# Voeding.net
KiCad netlist of a schematic drawn in Altium Designer
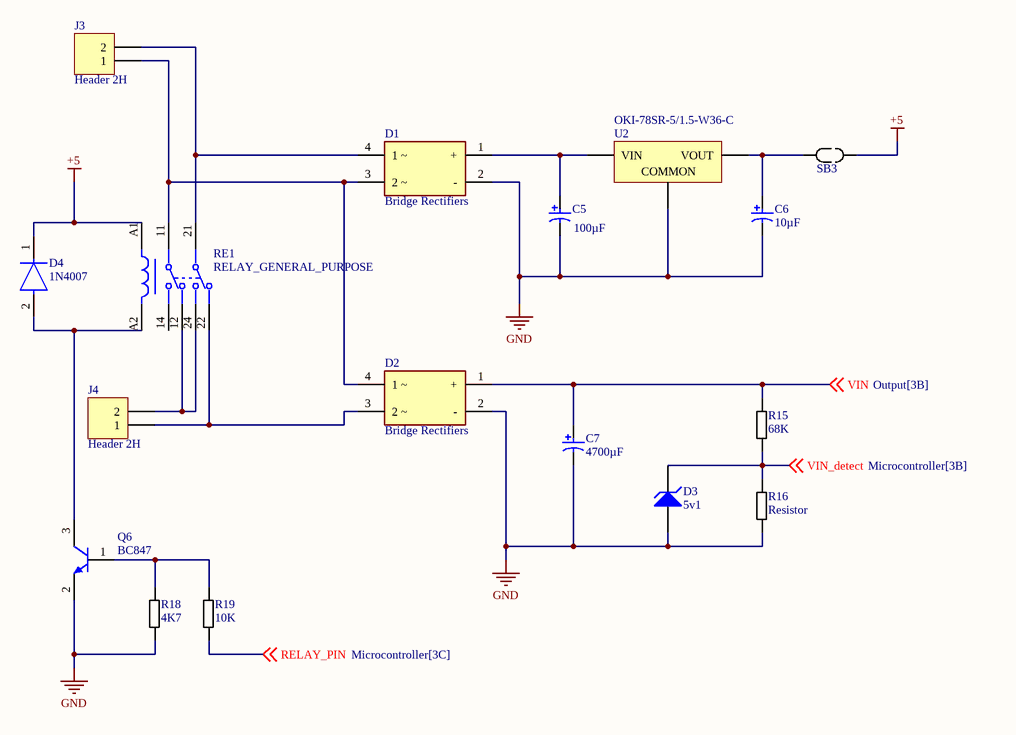
[diagram p0: Voeding.SchDoc]

(export (version "E")
  (design (tool "Eeschema 10.0.6"))
  (components
    (comp (ref "C5")
      (value "100µF")
      (footprint "CAP-SMD_BD8.0-L8.3-W8.3-FD")
      (fields (field (name "MANUFACTURER") "Panasonic"))
      (libsource (lib "Soldeerstation") (part "Electrolytic capacitor"))
    )
    (comp (ref "C6")
      (value "10µF")
      (footprint "CAP-SMD_BD4.0-L4.3-W4.3-FD-LS5.3")
      (fields (field (name "MANUFACTURER") "Panasonic"))
      (libsource (lib "Soldeerstation") (part "Electrolytic capacitor"))
    )
    (comp (ref "C7")
      (value "4700µF")
      (footprint "CAP-TH_BD25.0-P10.00-D1.4-FD")
      (fields (field (name "MANUFACTURER") "Panasonic"))
      (libsource (lib "Soldeerstation") (part "Electrolytic capacitor"))
    )
    (comp (ref "D1")
      (value "Bridge Rectifiers")
      (footprint "TTF")
      (fields
        (field (name "OCTOPART") "https://octopart.com/gbpc3510w+t0-taiwan+semiconductor-12450781")
        (field (name "MANUFACTURER PART NUMBER") "GBPC3510W T0")
        (field (name "MANUFACTURER") "Taiwan Semiconductor")
      )
      (libsource (lib "Soldeerstation") (part "Bridge Rectifiers"))
    )
    (comp (ref "D2")
      (value "Bridge Rectifiers")
      (footprint "TTF")
      (fields
        (field (name "OCTOPART") "https://octopart.com/gbpc3510w+t0-taiwan+semiconductor-12450781")
        (field (name "MANUFACTURER PART NUMBER") "GBPC3510W T0")
        (field (name "MANUFACTURER") "Taiwan Semiconductor")
      )
      (libsource (lib "Soldeerstation") (part "Bridge Rectifiers"))
    )
    (comp (ref "D3")
      (value "5v1")
      (footprint "FP-SOD123-IPC_C")
      (fields (field (name "MANUFACTURER") "On Semiconductor") (field (name "PARTNUMBER") "1SMB5928BT3G"))
      (libsource (lib "Soldeerstation") (part "Zener"))
    )
    (comp (ref "D4")
      (value "1N4007")
      (footprint "SOD-123FL")
      (fields
        (field (name "OCTOPART") "https://octopart.com/1n4007-e3%2F54-vishay-39548207")
        (field (name "MANUFACTURER") "Vishay")
        (field (name "MANUFACTURER PART NUMBER") "1N4007-E3/54")
      )
      (libsource (lib "Soldeerstation") (part "Diode"))
    )
    (comp (ref "J3")
      (value "Header 2H")
      (footprint "Connector_2x1_p_5mm")
      (description "Header, 2-Pin, Right Angle")
      (fields (field (name "PUBLISHER") "Altium Limited"))
      (libsource (lib "Miscellaneous Connectors") (part "Header 2H"))
    )
    (comp (ref "J4")
      (value "Header 2H")
      (footprint "Connector_2x1_p_5mm")
      (description "Header, 2-Pin, Right Angle")
      (fields (field (name "PUBLISHER") "Altium Limited"))
      (libsource (lib "Miscellaneous Connectors") (part "Header 2H"))
    )
    (comp (ref "Q6")
      (value "BC847")
      (footprint "FAIR-SOT23-3_V")
      (fields (field (name "MANUFACTURER") "On Semiconductor") (field (name "PARTNUMBER") "BC547BRL1G"))
      (libsource (lib "Soldeerstation") (part "NPN Transistor"))
    )
    (comp (ref "R15")
      (value "68K")
      (footprint "RESC2013X50X30ML20T20")
      (fields (field (name "MANUFACTURER") "Vishay Dale") (field (name "PART NUMBER") "CRCW08050000Z0EA"))
      (libsource (lib "Soldeerstation") (part "Resistor"))
    )
    (comp (ref "R16")
      (value "Resistor")
      (footprint "RESC2013X50X30ML20T20")
      (fields (field (name "MANUFACTURER") "Vishay Dale") (field (name "PART NUMBER") "CRCW08050000Z0EA"))
      (libsource (lib "Soldeerstation") (part "Resistor"))
    )
    (comp (ref "R18")
      (value "4K7")
      (footprint "RESC2013X50X30ML20T20")
      (fields (field (name "MANUFACTURER") "Vishay Dale") (field (name "PART NUMBER") "CRCW08050000Z0EA"))
      (libsource (lib "Soldeerstation") (part "Resistor"))
    )
    (comp (ref "R19")
      (value "10K")
      (footprint "RESC2013X50X30ML20T20")
      (fields (field (name "MANUFACTURER") "Vishay Dale") (field (name "PART NUMBER") "CRCW08050000Z0EA"))
      (libsource (lib "Soldeerstation") (part "Resistor"))
    )
    (comp (ref "RE1")
      (value "RELAY_GENERAL_PURPOSE")
      (footprint "RT42")
      (fields
        (field (name "MANUFACTURER PART NUMBER") "RT424005")
        (field (name "OCTOPART") "https://octopart.com/5-1393243-9-te+connectivity-41835766")
        (field (name "MANUFACTURER") "TE Connectivity")
      )
      (libsource (lib "Soldeerstation") (part "RELAY_GENERAL_PURPOSE"))
    )
    (comp (ref "SB3")
      (value "SolderBridge")
      (footprint "SolderBridge_BIG")
      (libsource (lib "Soldeerstation") (part "SolderBridge"))
    )
    (comp (ref "U2")
      (value "OKI-78SR-5/1.5-W36-C")
      (footprint "OKI78SR515W36C")
      (fields (field (name "MANUFACTURER") "Murata"))
      (libsource (lib "Soldeerstation") (part "DC/DC Converter"))
    )
  )
  (nets
    (net (code "1") (name "+5") (class "Default")
      (node (ref "D4") (pin "1") (pinfunction "C_1") (pintype "passive"))
      (node (ref "RE1") (pin "A1") (pinfunction "A1_A1") (pintype "passive"))
      (node (ref "SB3") (pin "2") (pinfunction "2_2") (pintype "passive"))
    )
    (net (code "2") (name "GND") (class "Default")
      (node (ref "C5") (pin "2") (pinfunction "-_2") (pintype "passive"))
      (node (ref "C6") (pin "2") (pinfunction "-_2") (pintype "passive"))
      (node (ref "C7") (pin "2") (pinfunction "-_2") (pintype "passive"))
      (node (ref "D1") (pin "2") (pinfunction "-_2") (pintype "passive"))
      (node (ref "D2") (pin "2") (pinfunction "-_2") (pintype "passive"))
      (node (ref "D3") (pin "2") (pinfunction "A_2") (pintype "passive"))
      (node (ref "Q6") (pin "2") (pinfunction "E_2") (pintype "passive"))
      (node (ref "R16") (pin "1") (pinfunction "1_1") (pintype "passive"))
      (node (ref "R18") (pin "1") (pinfunction "1_1") (pintype "passive"))
      (node (ref "U2") (pin "2") (pinfunction "COMMON_2") (pintype "power_in"))
    )
    (net (code "3") (name "Net-(C5-+)") (class "Default")
      (node (ref "C5") (pin "1") (pinfunction "+_1") (pintype "passive"))
      (node (ref "D1") (pin "1") (pinfunction "+_1") (pintype "passive"))
      (node (ref "U2") (pin "1") (pinfunction "VIN_1") (pintype "power_in"))
    )
    (net (code "4") (name "Net-(C6-+)") (class "Default")
      (node (ref "C6") (pin "1") (pinfunction "+_1") (pintype "passive"))
      (node (ref "SB3") (pin "1") (pinfunction "1_1") (pintype "passive"))
      (node (ref "U2") (pin "3") (pinfunction "VOUT_3") (pintype "power_in"))
    )
    (net (code "5") (name "Net-(D1-1_~)") (class "Default")
      (node (ref "D1") (pin "4") (pinfunction "1_~_4") (pintype "passive"))
      (node (ref "J3") (pin "2") (pinfunction "2_2") (pintype "passive"))
      (node (ref "RE1") (pin "21") (pinfunction "21_21") (pintype "passive"))
    )
    (net (code "6") (name "Net-(D1-2_~)") (class "Default")
      (node (ref "D1") (pin "3") (pinfunction "2_~_3") (pintype "passive"))
      (node (ref "D2") (pin "4") (pinfunction "1_~_4") (pintype "passive"))
      (node (ref "J3") (pin "1") (pinfunction "1_1") (pintype "passive"))
      (node (ref "RE1") (pin "11") (pinfunction "11_11") (pintype "passive"))
    )
    (net (code "7") (name "Net-(D2-2_~)") (class "Default")
      (node (ref "D2") (pin "3") (pinfunction "2_~_3") (pintype "passive"))
      (node (ref "J4") (pin "1") (pinfunction "1_1") (pintype "passive"))
      (node (ref "RE1") (pin "22") (pinfunction "22_22") (pintype "passive"))
    )
    (net (code "8") (name "Net-(D4-A)") (class "Default")
      (node (ref "D4") (pin "2") (pinfunction "A_2") (pintype "passive"))
      (node (ref "Q6") (pin "3") (pinfunction "C_3") (pintype "passive"))
      (node (ref "RE1") (pin "A2") (pinfunction "A2_A2") (pintype "passive"))
    )
    (net (code "9") (name "Net-(J4-Pad2)") (class "Default")
      (node (ref "J4") (pin "2") (pinfunction "2_2") (pintype "passive"))
      (node (ref "RE1") (pin "12") (pinfunction "12_12") (pintype "passive"))
      (node (ref "RE1") (pin "24") (pinfunction "24_24") (pintype "passive"))
    )
    (net (code "10") (name "Net-(Q6-B)") (class "Default")
      (node (ref "Q6") (pin "1") (pinfunction "B_1") (pintype "passive"))
      (node (ref "R18") (pin "2") (pinfunction "2_2") (pintype "passive"))
      (node (ref "R19") (pin "2") (pinfunction "2_2") (pintype "passive"))
    )
    (net (code "11") (name "RELAY_PIN") (class "Default")
      (node (ref "R19") (pin "1") (pinfunction "1_1") (pintype "passive"))
    )
    (net (code "12") (name "VIN") (class "Default")
      (node (ref "C7") (pin "1") (pinfunction "+_1") (pintype "passive"))
      (node (ref "D2") (pin "1") (pinfunction "+_1") (pintype "passive"))
      (node (ref "R15") (pin "2") (pinfunction "2_2") (pintype "passive"))
    )
    (net (code "13") (name "VIN_detect") (class "Default")
      (node (ref "D3") (pin "1") (pinfunction "K_1") (pintype "passive"))
      (node (ref "R15") (pin "1") (pinfunction "1_1") (pintype "passive"))
      (node (ref "R16") (pin "2") (pinfunction "2_2") (pintype "passive"))
    )
    (net (code "14") (name "unconnected-(RE1-Pad14)") (class "Default")
      (node (ref "RE1") (pin "14") (pinfunction "14_14") (pintype "passive"))
    )
  )
)
